# Oscillator_11_059200MHz.net
KiCad netlist of a schematic drawn in Altium Designer
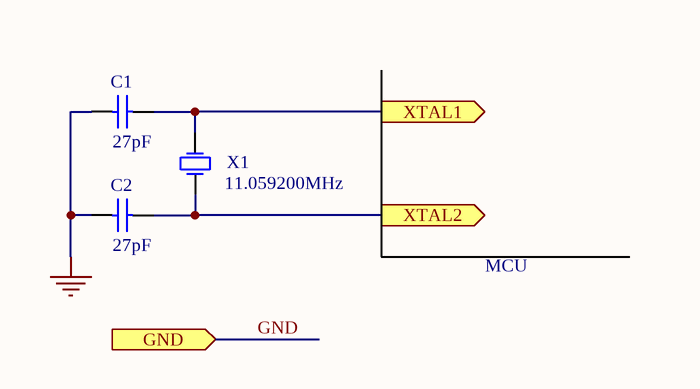
[diagram p0: Oscillator_11.059200MHz.SchDoc]

(export (version "E")
  (design (tool "Eeschema 10.0.6"))
  (components
    (comp (ref "C1")
      (value "27pF")
      (footprint "CAPNTO2.54-3.56x2.03")
      (description "Capacitor")
      (fields
        (field (name "MANUFACTURER") "Generic Components")
        (field (name "Comment") "Cap")
        (field (name "PUBLISHER") "Altium Limited")
      )
      (libsource (lib "Miscellaneous Devices") (part "Cap"))
    )
    (comp (ref "C2")
      (value "27pF")
      (footprint "CAPNTO2.54-3.56x2.03")
      (description "Capacitor")
      (fields
        (field (name "MANUFACTURER") "Generic Components")
        (field (name "Comment") "Cap")
        (field (name "PUBLISHER") "Altium Limited")
      )
      (libsource (lib "Miscellaneous Devices") (part "Cap"))
    )
    (comp (ref "X1")
      (value "11.059200MHz")
      (footprint "XTAL_1")
      (description "Crystal Oscillator")
      (fields
        (field (name "MANUFACTURER") "Generic Components")
        (field (name "Comment") "XTAL")
        (field (name "PUBLISHER") "Altium Limited")
      )
      (libsource (lib "my Libraries") (part "XTAL"))
    )
  )
  (nets
    (net (code "1") (name "/XTAL1") (class "Default")
      (node (ref "C1") (pin "2") (pinfunction "2_2") (pintype "passive"))
      (node (ref "X1") (pin "2") (pinfunction "OSC2_2") (pintype "passive"))
    )
    (net (code "2") (name "/XTAL2") (class "Default")
      (node (ref "C2") (pin "2") (pinfunction "2_2") (pintype "passive"))
      (node (ref "X1") (pin "1") (pinfunction "OSC1_1") (pintype "passive"))
    )
    (net (code "3") (name "GND") (class "Default")
      (node (ref "C1") (pin "1") (pinfunction "1_1") (pintype "passive"))
      (node (ref "C2") (pin "1") (pinfunction "1_1") (pintype "passive"))
    )
  )
)
